# top.net
KiCad netlist of a schematic drawn in Altium Designer
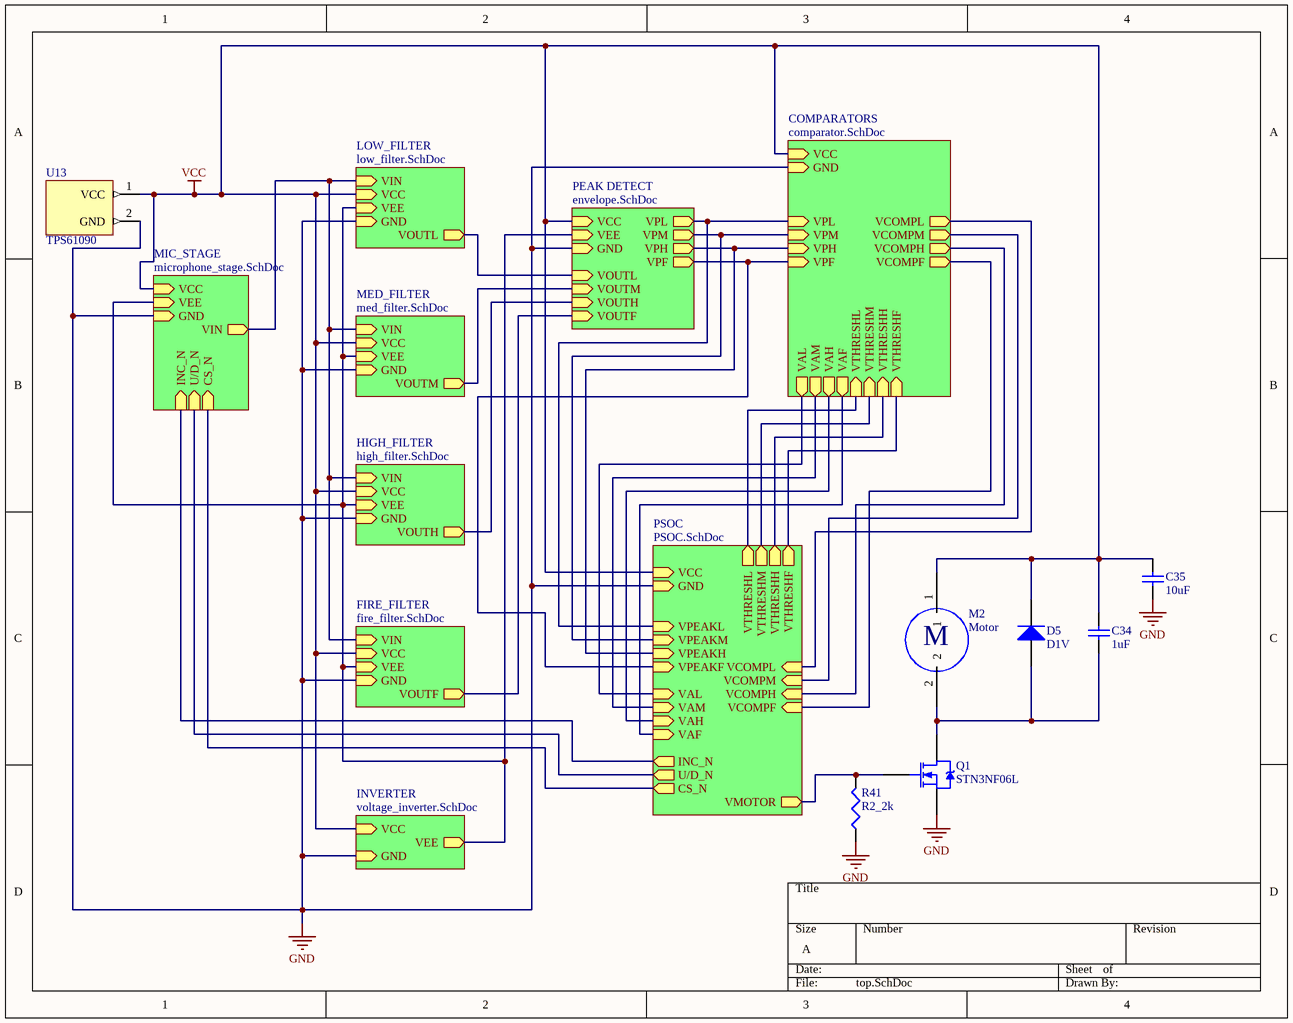
[diagram p0: top.SchDoc]

(export (version "E")
  (design (tool "Eeschema 10.0.6"))
  (components
    (comp (ref "C34")
      (value "1uF")
      (footprint "C0603")
      (description "1 uF Surface Mount Capacitor")
      (fields
        (field (name "MANUFACTURER") "Murata Electronics North America")
        (field (name "MANUFACTURER PART NUMBER") "GRM188R61C105KA93D")
      )
      (libsource (lib "Capstone Libraries") (part "C1uF"))
    )
    (comp (ref "C35")
      (value "10uF")
      (footprint "C0603")
      (description "10 uF Surface Mount Capacitor")
      (fields
        (field (name "MANUFACTURER") "Yageo")
        (field (name "MANUFACTURER PART NUMBER") "CC0603KRX5R5BB106")
      )
      (libsource (lib "Capstone Libraries") (part "C10uF"))
    )
    (comp (ref "D5")
      (value "D1V")
      (footprint "D1206")
      (description "Standard 1V Diode")
      (fields
        (field (name "MANUFACTURER") "Bourns Inc.")
        (field (name "MANUFACTURER PART NUMBER") "CD1206-S01575")
      )
      (libsource (lib "Capstone Libraries") (part "D1V"))
    )
    (comp (ref "M2")
      (value "Motor")
      (footprint "B2B-PH-K-S")
      (fields
        (field (name "MANUFACTURER") "JST Sales America Inc.")
        (field (name "MANUFACTURER PART NUMBER") "B2B-PH-K-S(LF)(SN)")
      )
      (libsource (lib "Capstone Libraries") (part "Motor"))
    )
    (comp (ref "Q1")
      (value "STN3NF06L")
      (footprint "SOT-223")
      (description "N-Channel 4A Power MOSFET")
      (fields (field (name "MANUFACTURER") "STMicroelectronics"))
      (libsource (lib "Capstone Libraries") (part "STN3NF06L"))
    )
    (comp (ref "R41")
      (value "R2_2k")
      (footprint "R0603")
      (description "2.2k Ohms Surface Mount Resistor")
      (fields
        (field (name "MANUFACTURER") "Yageo")
        (field (name "MANUFACTURER PART NUMBER") "RC0603FR-072K2L")
      )
      (libsource (lib "Capstone Libraries") (part "R2_2k"))
    )
    (comp (ref "U13")
      (value "TPS61090")
      (footprint "B2B-PH-K-S")
      (description "Power Electronics Connector")
      (fields
        (field (name "MANUFACTURER") "JST Sales America Inc.")
        (field (name "MANUFACTURER PART NUMBER") "B2B-PH-K-S(LF)(SN)")
      )
      (libsource (lib "Capstone Libraries") (part "TPS61090"))
    )
  )
  (nets
    (net (code "14") (name "/VMOTOR") (class "Default")
      (node (ref "Q1") (pin "1") (pinfunction "G_1") (pintype "passive"))
      (node (ref "R41") (pin "2") (pinfunction "2_2") (pintype "passive"))
    )
    (net (code "27") (name "GND") (class "Default")
      (node (ref "C35") (pin "1") (pinfunction "1_1") (pintype "passive"))
      (node (ref "Q1") (pin "3") (pinfunction "S_3") (pintype "passive"))
      (node (ref "R41") (pin "1") (pinfunction "1_1") (pintype "passive"))
      (node (ref "U13") (pin "2") (pinfunction "GND_2") (pintype "output"))
    )
    (net (code "28") (name "Net-(D5-A)") (class "Default")
      (node (ref "C34") (pin "1") (pinfunction "1_1") (pintype "passive"))
      (node (ref "D5") (pin "1") (pinfunction "A_1") (pintype "passive"))
      (node (ref "M2") (pin "2") (pinfunction "2_2") (pintype "passive"))
      (node (ref "Q1") (pin "2") (pinfunction "D_2") (pintype "passive"))
    )
    (net (code "29") (name "VCC") (class "Default")
      (node (ref "C34") (pin "2") (pinfunction "2_2") (pintype "passive"))
      (node (ref "C35") (pin "2") (pinfunction "2_2") (pintype "passive"))
      (node (ref "D5") (pin "2") (pinfunction "K_2") (pintype "passive"))
      (node (ref "M2") (pin "1") (pinfunction "1_1") (pintype "passive"))
      (node (ref "U13") (pin "1") (pinfunction "VCC_1") (pintype "output"))
    )
  )
)
